# LED_7_Series.net
KiCad netlist of a schematic drawn in Altium Designer
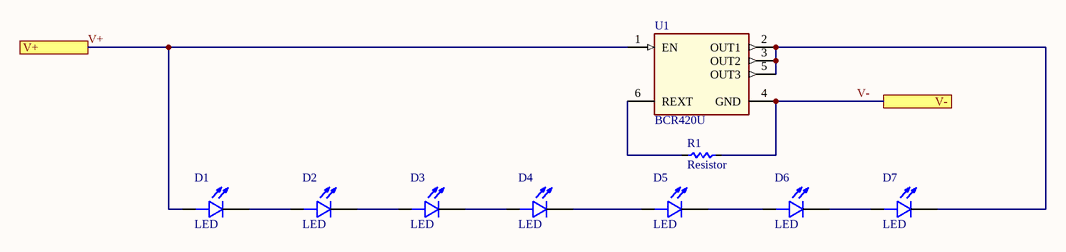
[diagram p0: LED_7_Series.SchDoc]

(export (version "E")
  (design (tool "Eeschema 10.0.6"))
  (components
    (comp (ref "D1") (value "LED") (footprint "LED2835N") (libsource (lib "LED SchLib") (part "LED")))
    (comp (ref "D2") (value "LED") (footprint "LED2835N") (libsource (lib "LED SchLib") (part "LED")))
    (comp (ref "D3") (value "LED") (footprint "LED2835N") (libsource (lib "LED SchLib") (part "LED")))
    (comp (ref "D4") (value "LED") (footprint "LED2835N") (libsource (lib "LED SchLib") (part "LED")))
    (comp (ref "D5") (value "LED") (footprint "LED2835N") (libsource (lib "LED SchLib") (part "LED")))
    (comp (ref "D6") (value "LED") (footprint "LED2835N") (libsource (lib "LED SchLib") (part "LED")))
    (comp (ref "D7") (value "LED") (footprint "LED2835N") (libsource (lib "LED SchLib") (part "LED")))
    (comp (ref "R1")
      (value "Resistor")
      (footprint "RES1206")
      (libsource (lib "LED SchLib") (part "Resistor"))
    )
    (comp (ref "U1") (value "BCR420U") (footprint "BCR420U") (libsource (lib "LED SchLib") (part "BCR420U")))
  )
  (nets
    (net (code "1") (name "/V+") (class "Default")
      (node (ref "D1") (pin "A") (pinfunction "A_A") (pintype "passive"))
      (node (ref "U1") (pin "1") (pinfunction "EN_1") (pintype "input"))
    )
    (net (code "2") (name "/V-") (class "Default")
      (node (ref "R1") (pin "1") (pinfunction "1_1") (pintype "passive"))
      (node (ref "U1") (pin "4") (pinfunction "GND_4") (pintype "power_in"))
    )
    (net (code "3") (name "Net-(D1-PadC)") (class "Default")
      (node (ref "D1") (pin "C") (pinfunction "C_C") (pintype "passive"))
      (node (ref "D2") (pin "A") (pinfunction "A_A") (pintype "passive"))
    )
    (net (code "4") (name "Net-(D2-PadC)") (class "Default")
      (node (ref "D2") (pin "C") (pinfunction "C_C") (pintype "passive"))
      (node (ref "D3") (pin "A") (pinfunction "A_A") (pintype "passive"))
    )
    (net (code "5") (name "Net-(D3-PadC)") (class "Default")
      (node (ref "D3") (pin "C") (pinfunction "C_C") (pintype "passive"))
      (node (ref "D4") (pin "A") (pinfunction "A_A") (pintype "passive"))
    )
    (net (code "6") (name "Net-(D4-PadC)") (class "Default")
      (node (ref "D4") (pin "C") (pinfunction "C_C") (pintype "passive"))
      (node (ref "D5") (pin "A") (pinfunction "A_A") (pintype "passive"))
    )
    (net (code "7") (name "Net-(D5-PadC)") (class "Default")
      (node (ref "D5") (pin "C") (pinfunction "C_C") (pintype "passive"))
      (node (ref "D6") (pin "A") (pinfunction "A_A") (pintype "passive"))
    )
    (net (code "8") (name "Net-(D6-PadC)") (class "Default")
      (node (ref "D6") (pin "C") (pinfunction "C_C") (pintype "passive"))
      (node (ref "D7") (pin "A") (pinfunction "A_A") (pintype "passive"))
    )
    (net (code "9") (name "Net-(U1-OUT1)") (class "Default")
      (node (ref "D7") (pin "C") (pinfunction "C_C") (pintype "passive"))
      (node (ref "U1") (pin "2") (pinfunction "OUT1_2") (pintype "output"))
      (node (ref "U1") (pin "3") (pinfunction "OUT2_3") (pintype "output"))
      (node (ref "U1") (pin "5") (pinfunction "OUT3_5") (pintype "output"))
    )
    (net (code "10") (name "Net-(U1-REXT)") (class "Default")
      (node (ref "R1") (pin "2") (pinfunction "2_2") (pintype "passive"))
      (node (ref "U1") (pin "6") (pinfunction "REXT_6") (pintype "passive"))
    )
  )
)
